# AS3364_DG412_bus_mixer_v1_4-4-layer.net
KiCad netlist of a schematic drawn in EAGLE
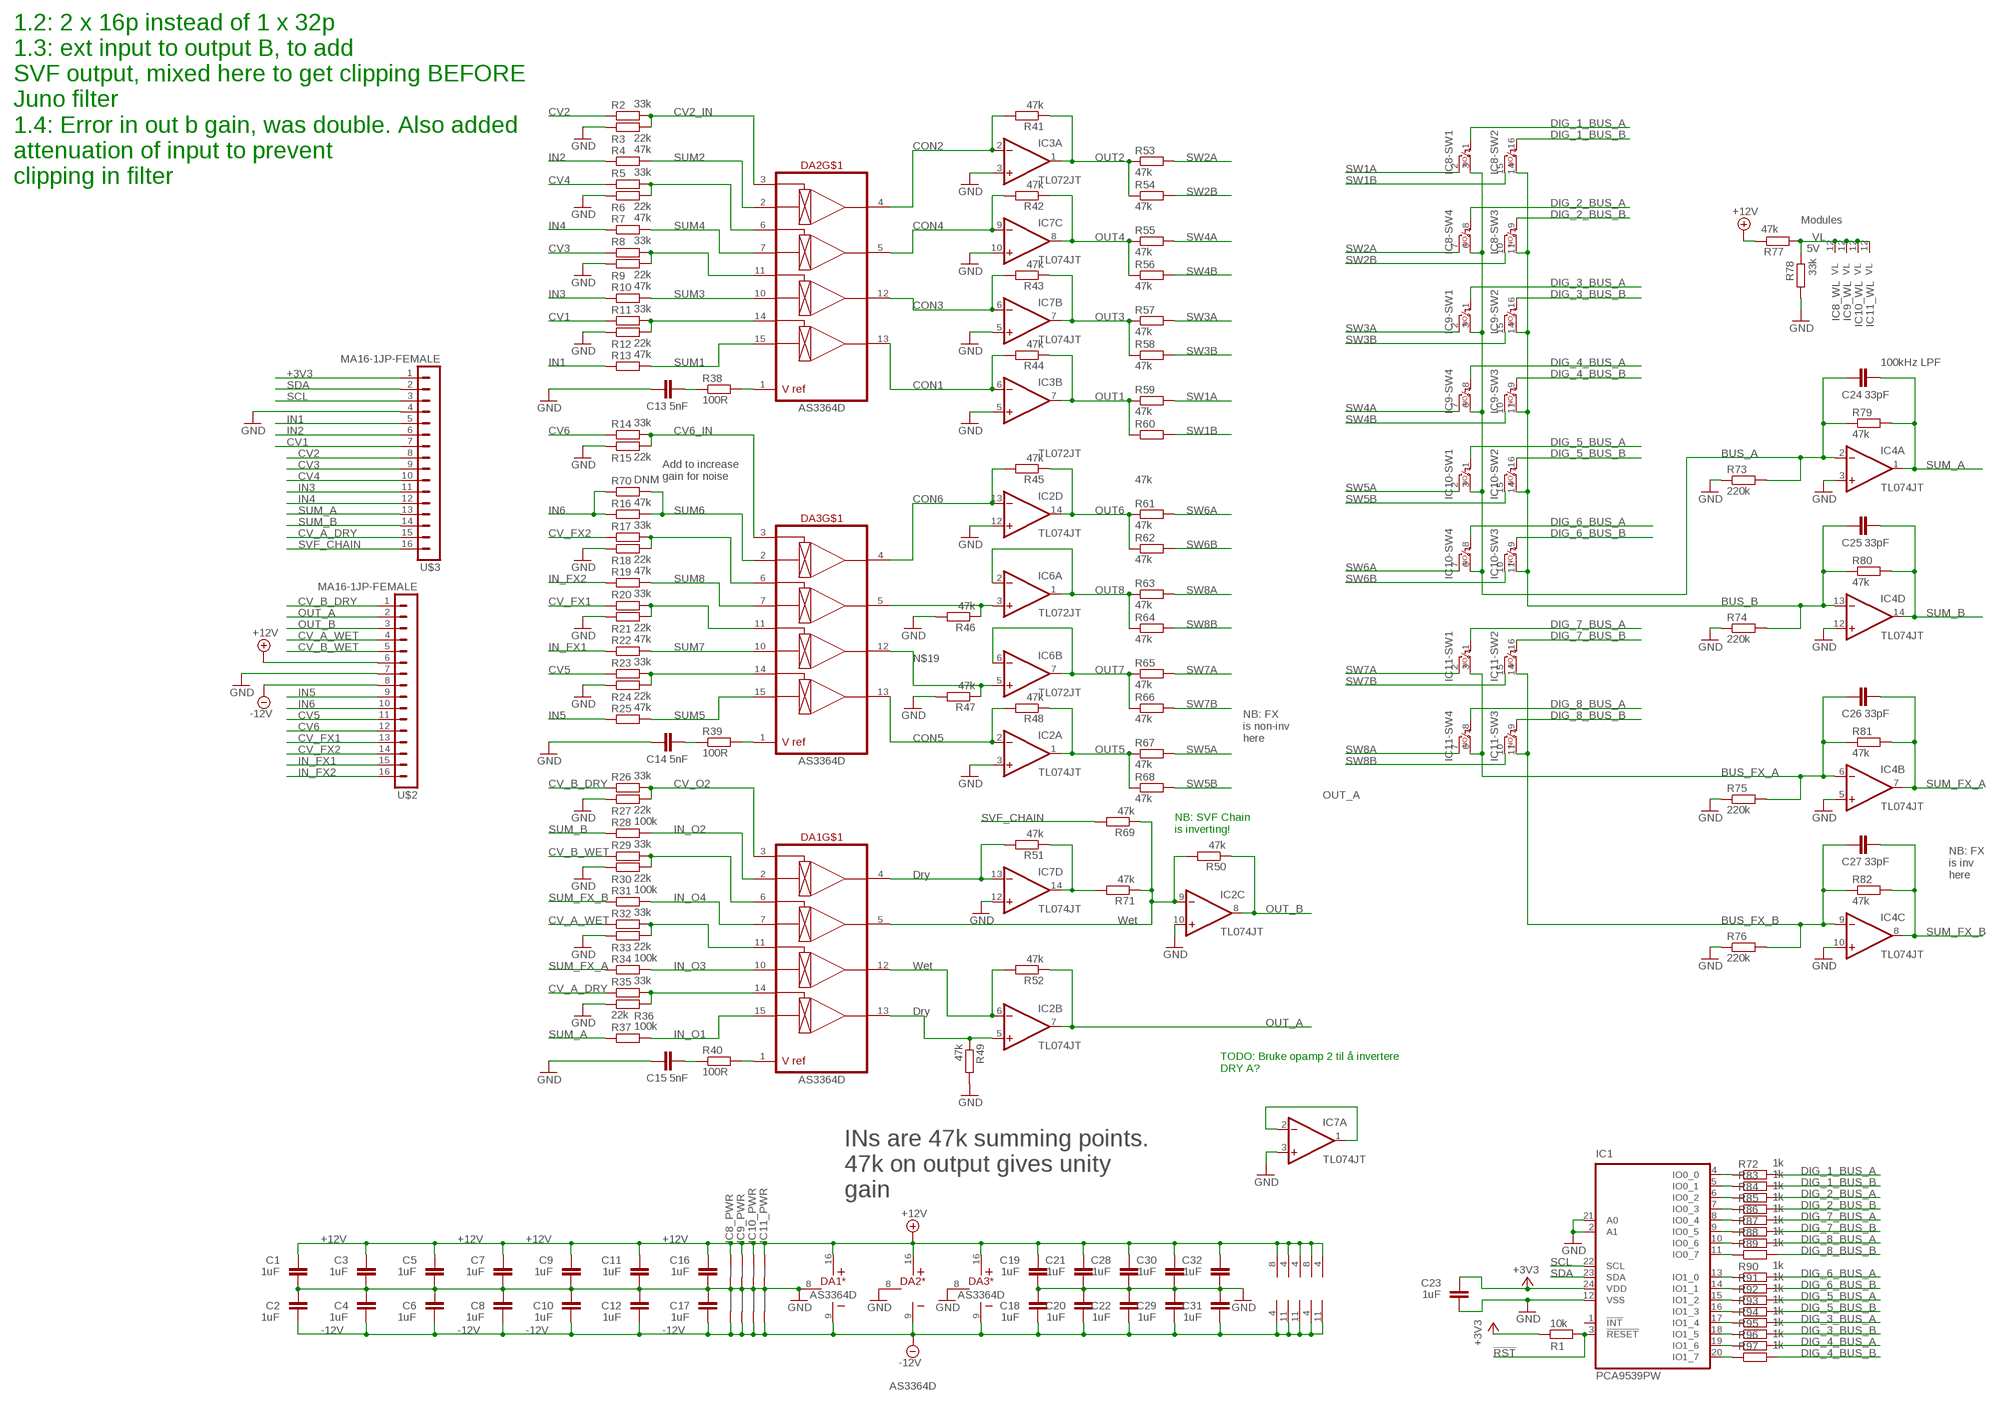
[diagram p0: schematic, sheet 1]

(export (version "E")
  (design (tool "Eeschema 10.0.6"))
  (components
    (comp (ref "C1")
      (value "1uF")
      (footprint "eagle-import:C0402-J")
      (libsource (lib "eagle-import") (part "C-EU-J0402"))
    )
    (comp (ref "C2")
      (value "1uF")
      (footprint "eagle-import:C0402-J")
      (libsource (lib "eagle-import") (part "C-EU-J0402"))
    )
    (comp (ref "C3")
      (value "1uF")
      (footprint "eagle-import:C0402-J")
      (libsource (lib "eagle-import") (part "C-EU-J0402"))
    )
    (comp (ref "C4")
      (value "1uF")
      (footprint "eagle-import:C0402-J")
      (libsource (lib "eagle-import") (part "C-EU-J0402"))
    )
    (comp (ref "C5")
      (value "1uF")
      (footprint "eagle-import:C0402-J")
      (libsource (lib "eagle-import") (part "C-EU-J0402"))
    )
    (comp (ref "C6")
      (value "1uF")
      (footprint "eagle-import:C0402-J")
      (libsource (lib "eagle-import") (part "C-EU-J0402"))
    )
    (comp (ref "C7")
      (value "1uF")
      (footprint "eagle-import:C0402-J")
      (libsource (lib "eagle-import") (part "C-EU-J0402"))
    )
    (comp (ref "C8")
      (value "1uF")
      (footprint "eagle-import:C0402-J")
      (libsource (lib "eagle-import") (part "C-EU-J0402"))
    )
    (comp (ref "C9")
      (value "1uF")
      (footprint "eagle-import:C0402-J")
      (libsource (lib "eagle-import") (part "C-EU-J0402"))
    )
    (comp (ref "C10")
      (value "1uF")
      (footprint "eagle-import:C0402-J")
      (libsource (lib "eagle-import") (part "C-EU-J0402"))
    )
    (comp (ref "C11")
      (value "1uF")
      (footprint "eagle-import:C0402-J")
      (libsource (lib "eagle-import") (part "C-EU-J0402"))
    )
    (comp (ref "C12")
      (value "1uF")
      (footprint "eagle-import:C0402-J")
      (libsource (lib "eagle-import") (part "C-EU-J0402"))
    )
    (comp (ref "C13")
      (value "5nF")
      (footprint "eagle-import:C0402-J")
      (libsource (lib "eagle-import") (part "C-EU-J0402"))
    )
    (comp (ref "C14")
      (value "5nF")
      (footprint "eagle-import:C0402-J")
      (libsource (lib "eagle-import") (part "C-EU-J0402"))
    )
    (comp (ref "C15")
      (value "5nF")
      (footprint "eagle-import:C0402-J")
      (libsource (lib "eagle-import") (part "C-EU-J0402"))
    )
    (comp (ref "C16")
      (value "1uF")
      (footprint "eagle-import:C0402-J")
      (libsource (lib "eagle-import") (part "C-EU-J0402"))
    )
    (comp (ref "C17")
      (value "1uF")
      (footprint "eagle-import:C0402-J")
      (libsource (lib "eagle-import") (part "C-EU-J0402"))
    )
    (comp (ref "C18")
      (value "1uF")
      (footprint "eagle-import:C0402-J")
      (libsource (lib "eagle-import") (part "C-EU-J0402"))
    )
    (comp (ref "C19")
      (value "1uF")
      (footprint "eagle-import:C0402-J")
      (libsource (lib "eagle-import") (part "C-EU-J0402"))
    )
    (comp (ref "C20")
      (value "1uF")
      (footprint "eagle-import:C0402-J")
      (libsource (lib "eagle-import") (part "C-EU-J0402"))
    )
    (comp (ref "C21")
      (value "1uF")
      (footprint "eagle-import:C0402-J")
      (libsource (lib "eagle-import") (part "C-EU-J0402"))
    )
    (comp (ref "C22")
      (value "1uF")
      (footprint "eagle-import:C0402-J")
      (libsource (lib "eagle-import") (part "C-EU-J0402"))
    )
    (comp (ref "C23")
      (value "1uF")
      (footprint "eagle-import:C0402-J")
      (libsource (lib "eagle-import") (part "C-EU-J0402"))
    )
    (comp (ref "C24")
      (value "33pF")
      (footprint "eagle-import:C0402-J")
      (libsource (lib "eagle-import") (part "C-EU-J0402"))
    )
    (comp (ref "C25")
      (value "33pF")
      (footprint "eagle-import:C0402-J")
      (libsource (lib "eagle-import") (part "C-EU-J0402"))
    )
    (comp (ref "C26")
      (value "33pF")
      (footprint "eagle-import:C0402-J")
      (libsource (lib "eagle-import") (part "C-EU-J0402"))
    )
    (comp (ref "C27")
      (value "33pF")
      (footprint "eagle-import:C0402-J")
      (libsource (lib "eagle-import") (part "C-EU-J0402"))
    )
    (comp (ref "C28")
      (value "1uF")
      (footprint "eagle-import:C0402-J")
      (libsource (lib "eagle-import") (part "C-EU-J0402"))
    )
    (comp (ref "C29")
      (value "1uF")
      (footprint "eagle-import:C0402-J")
      (libsource (lib "eagle-import") (part "C-EU-J0402"))
    )
    (comp (ref "C30")
      (value "1uF")
      (footprint "eagle-import:C0402-J")
      (libsource (lib "eagle-import") (part "C-EU-J0402"))
    )
    (comp (ref "C31")
      (value "1uF")
      (footprint "eagle-import:C0402-J")
      (libsource (lib "eagle-import") (part "C-EU-J0402"))
    )
    (comp (ref "C32")
      (value "1uF")
      (footprint "eagle-import:C0402-J")
      (libsource (lib "eagle-import") (part "C-EU-J0402"))
    )
    (comp (ref "DA1")
      (value "AS3364D")
      (footprint "eagle-import:DIL16J")
      (libsource (lib "eagle-import") (part "AS3364D"))
    )
    (comp (ref "DA2")
      (value "AS3364D")
      (footprint "eagle-import:DIL16J")
      (libsource (lib "eagle-import") (part "AS3364D"))
    )
    (comp (ref "DA3")
      (value "AS3364D")
      (footprint "eagle-import:DIL16J")
      (libsource (lib "eagle-import") (part "AS3364D"))
    )
    (comp (ref "IC1")
      (value "PCA9539PW")
      (footprint "eagle-import:TSSOP24J")
      (libsource (lib "eagle-import") (part "PCA9539PW"))
    )
    (comp (ref "IC2")
      (value "TL074JT")
      (footprint "eagle-import:TSSOP14J")
      (libsource (lib "eagle-import") (part "TL074JT"))
    )
    (comp (ref "IC3")
      (value "TL072JT")
      (footprint "eagle-import:TSSOP8J")
      (libsource (lib "eagle-import") (part "TL072JT"))
    )
    (comp (ref "IC4")
      (value "TL074JT")
      (footprint "eagle-import:TSSOP14J")
      (libsource (lib "eagle-import") (part "TL074JT"))
    )
    (comp (ref "IC6")
      (value "TL072JT")
      (footprint "eagle-import:TSSOP8J")
      (libsource (lib "eagle-import") (part "TL072JT"))
    )
    (comp (ref "IC7")
      (value "TL074JT")
      (footprint "eagle-import:TSSOP14J")
      (libsource (lib "eagle-import") (part "TL074JT"))
    )
    (comp (ref "IC8")
      (value "DG412-J")
      (footprint "eagle-import:DIL16J")
      (libsource (lib "eagle-import") (part "DG412-J"))
    )
    (comp (ref "IC9")
      (value "DG412-J")
      (footprint "eagle-import:DIL16J")
      (libsource (lib "eagle-import") (part "DG412-J"))
    )
    (comp (ref "IC10")
      (value "DG412-J")
      (footprint "eagle-import:DIL16J")
      (libsource (lib "eagle-import") (part "DG412-J"))
    )
    (comp (ref "IC11")
      (value "DG412-J")
      (footprint "eagle-import:DIL16J")
      (libsource (lib "eagle-import") (part "DG412-J"))
    )
    (comp (ref "R1")
      (value "10k")
      (footprint "eagle-import:R0402")
      (libsource (lib "eagle-import") (part "R-EU_R0402"))
    )
    (comp (ref "R2")
      (value "33k")
      (footprint "eagle-import:R0402")
      (libsource (lib "eagle-import") (part "R-EU_R0402"))
    )
    (comp (ref "R3")
      (value "22k")
      (footprint "eagle-import:R0402")
      (libsource (lib "eagle-import") (part "R-EU_R0402"))
    )
    (comp (ref "R4")
      (value "47k")
      (footprint "eagle-import:R0402")
      (libsource (lib "eagle-import") (part "R-EU_R0402"))
    )
    (comp (ref "R5")
      (value "33k")
      (footprint "eagle-import:R0402")
      (libsource (lib "eagle-import") (part "R-EU_R0402"))
    )
    (comp (ref "R6")
      (value "22k")
      (footprint "eagle-import:R0402")
      (libsource (lib "eagle-import") (part "R-EU_R0402"))
    )
    (comp (ref "R7")
      (value "47k")
      (footprint "eagle-import:R0402")
      (libsource (lib "eagle-import") (part "R-EU_R0402"))
    )
    (comp (ref "R8")
      (value "33k")
      (footprint "eagle-import:R0402")
      (libsource (lib "eagle-import") (part "R-EU_R0402"))
    )
    (comp (ref "R9")
      (value "22k")
      (footprint "eagle-import:R0402")
      (libsource (lib "eagle-import") (part "R-EU_R0402"))
    )
    (comp (ref "R10")
      (value "47k")
      (footprint "eagle-import:R0402")
      (libsource (lib "eagle-import") (part "R-EU_R0402"))
    )
    (comp (ref "R11")
      (value "33k")
      (footprint "eagle-import:R0402")
      (libsource (lib "eagle-import") (part "R-EU_R0402"))
    )
    (comp (ref "R12")
      (value "22k")
      (footprint "eagle-import:R0402")
      (libsource (lib "eagle-import") (part "R-EU_R0402"))
    )
    (comp (ref "R13")
      (value "47k")
      (footprint "eagle-import:R0402")
      (libsource (lib "eagle-import") (part "R-EU_R0402"))
    )
    (comp (ref "R14")
      (value "33k")
      (footprint "eagle-import:R0402")
      (libsource (lib "eagle-import") (part "R-EU_R0402"))
    )
    (comp (ref "R15")
      (value "22k")
      (footprint "eagle-import:R0402")
      (libsource (lib "eagle-import") (part "R-EU_R0402"))
    )
    (comp (ref "R16")
      (value "47k")
      (footprint "eagle-import:R0402")
      (libsource (lib "eagle-import") (part "R-EU_R0402"))
    )
    (comp (ref "R17")
      (value "33k")
      (footprint "eagle-import:R0402")
      (libsource (lib "eagle-import") (part "R-EU_R0402"))
    )
    (comp (ref "R18")
      (value "22k")
      (footprint "eagle-import:R0402")
      (libsource (lib "eagle-import") (part "R-EU_R0402"))
    )
    (comp (ref "R19")
      (value "47k")
      (footprint "eagle-import:R0402")
      (libsource (lib "eagle-import") (part "R-EU_R0402"))
    )
    (comp (ref "R20")
      (value "33k")
      (footprint "eagle-import:R0402")
      (libsource (lib "eagle-import") (part "R-EU_R0402"))
    )
    (comp (ref "R21")
      (value "22k")
      (footprint "eagle-import:R0402")
      (libsource (lib "eagle-import") (part "R-EU_R0402"))
    )
    (comp (ref "R22")
      (value "47k")
      (footprint "eagle-import:R0402")
      (libsource (lib "eagle-import") (part "R-EU_R0402"))
    )
    (comp (ref "R23")
      (value "33k")
      (footprint "eagle-import:R0402")
      (libsource (lib "eagle-import") (part "R-EU_R0402"))
    )
    (comp (ref "R24")
      (value "22k")
      (footprint "eagle-import:R0402")
      (libsource (lib "eagle-import") (part "R-EU_R0402"))
    )
    (comp (ref "R25")
      (value "47k")
      (footprint "eagle-import:R0402")
      (libsource (lib "eagle-import") (part "R-EU_R0402"))
    )
    (comp (ref "R26")
      (value "33k")
      (footprint "eagle-import:R0402")
      (libsource (lib "eagle-import") (part "R-EU_R0402"))
    )
    (comp (ref "R27")
      (value "22k")
      (footprint "eagle-import:R0402")
      (libsource (lib "eagle-import") (part "R-EU_R0402"))
    )
    (comp (ref "R28")
      (value "100k")
      (footprint "eagle-import:R0402")
      (libsource (lib "eagle-import") (part "R-EU_R0402"))
    )
    (comp (ref "R29")
      (value "33k")
      (footprint "eagle-import:R0402")
      (libsource (lib "eagle-import") (part "R-EU_R0402"))
    )
    (comp (ref "R30")
      (value "22k")
      (footprint "eagle-import:R0402")
      (libsource (lib "eagle-import") (part "R-EU_R0402"))
    )
    (comp (ref "R31")
      (value "100k")
      (footprint "eagle-import:R0402")
      (libsource (lib "eagle-import") (part "R-EU_R0402"))
    )
    (comp (ref "R32")
      (value "33k")
      (footprint "eagle-import:R0402")
      (libsource (lib "eagle-import") (part "R-EU_R0402"))
    )
    (comp (ref "R33")
      (value "22k")
      (footprint "eagle-import:R0402")
      (libsource (lib "eagle-import") (part "R-EU_R0402"))
    )
    (comp (ref "R34")
      (value "100k")
      (footprint "eagle-import:R0402")
      (libsource (lib "eagle-import") (part "R-EU_R0402"))
    )
    (comp (ref "R35")
      (value "33k")
      (footprint "eagle-import:R0402")
      (libsource (lib "eagle-import") (part "R-EU_R0402"))
    )
    (comp (ref "R36")
      (value "22k")
      (footprint "eagle-import:R0402")
      (libsource (lib "eagle-import") (part "R-EU_R0402"))
    )
    (comp (ref "R37")
      (value "100k")
      (footprint "eagle-import:R0402")
      (libsource (lib "eagle-import") (part "R-EU_R0402"))
    )
    (comp (ref "R38")
      (value "100R")
      (footprint "eagle-import:R0402")
      (libsource (lib "eagle-import") (part "R-EU_R0402"))
    )
    (comp (ref "R39")
      (value "100R")
      (footprint "eagle-import:R0402")
      (libsource (lib "eagle-import") (part "R-EU_R0402"))
    )
    (comp (ref "R40")
      (value "100R")
      (footprint "eagle-import:R0402")
      (libsource (lib "eagle-import") (part "R-EU_R0402"))
    )
    (comp (ref "R41")
      (value "47k")
      (footprint "eagle-import:R0402")
      (libsource (lib "eagle-import") (part "R-EU_R0402"))
    )
    (comp (ref "R42")
      (value "47k")
      (footprint "eagle-import:R0402")
      (libsource (lib "eagle-import") (part "R-EU_R0402"))
    )
    (comp (ref "R43")
      (value "47k")
      (footprint "eagle-import:R0402")
      (libsource (lib "eagle-import") (part "R-EU_R0402"))
    )
    (comp (ref "R44")
      (value "47k")
      (footprint "eagle-import:R0402")
      (libsource (lib "eagle-import") (part "R-EU_R0402"))
    )
    (comp (ref "R45")
      (value "47k")
      (footprint "eagle-import:R0402")
      (libsource (lib "eagle-import") (part "R-EU_R0402"))
    )
    (comp (ref "R46")
      (value "47k")
      (footprint "eagle-import:R0402")
      (libsource (lib "eagle-import") (part "R-EU_R0402"))
    )
    (comp (ref "R47")
      (value "47k")
      (footprint "eagle-import:R0402")
      (libsource (lib "eagle-import") (part "R-EU_R0402"))
    )
    (comp (ref "R48")
      (value "47k")
      (footprint "eagle-import:R0402")
      (libsource (lib "eagle-import") (part "R-EU_R0402"))
    )
    (comp (ref "R49")
      (value "47k")
      (footprint "eagle-import:R0402")
      (libsource (lib "eagle-import") (part "R-EU_R0402"))
    )
    (comp (ref "R50")
      (value "47k")
      (footprint "eagle-import:R0402")
      (libsource (lib "eagle-import") (part "R-EU_R0402"))
    )
    (comp (ref "R51")
      (value "47k")
      (footprint "eagle-import:R0402")
      (libsource (lib "eagle-import") (part "R-EU_R0402"))
    )
    (comp (ref "R52")
      (value "47k")
      (footprint "eagle-import:R0402")
      (libsource (lib "eagle-import") (part "R-EU_R0402"))
    )
    (comp (ref "R53")
      (value "47k")
      (footprint "eagle-import:R0402")
      (libsource (lib "eagle-import") (part "R-EU_R0402"))
    )
    (comp (ref "R54")
      (value "47k")
      (footprint "eagle-import:R0402")
      (libsource (lib "eagle-import") (part "R-EU_R0402"))
    )
    (comp (ref "R55")
      (value "47k")
      (footprint "eagle-import:R0402")
      (libsource (lib "eagle-import") (part "R-EU_R0402"))
    )
    (comp (ref "R56")
      (value "47k")
      (footprint "eagle-import:R0402")
      (libsource (lib "eagle-import") (part "R-EU_R0402"))
    )
    (comp (ref "R57")
      (value "47k")
      (footprint "eagle-import:R0402")
      (libsource (lib "eagle-import") (part "R-EU_R0402"))
    )
    (comp (ref "R58")
      (value "47k")
      (footprint "eagle-import:R0402")
      (libsource (lib "eagle-import") (part "R-EU_R0402"))
    )
    (comp (ref "R59")
      (value "47k")
      (footprint "eagle-import:R0402")
      (libsource (lib "eagle-import") (part "R-EU_R0402"))
    )
    (comp (ref "R60")
      (value "47k")
      (footprint "eagle-import:R0402")
      (libsource (lib "eagle-import") (part "R-EU_R0402"))
    )
    (comp (ref "R61")
      (value "47k")
      (footprint "eagle-import:R0402")
      (libsource (lib "eagle-import") (part "R-EU_R0402"))
    )
    (comp (ref "R62")
      (value "47k")
      (footprint "eagle-import:R0402")
      (libsource (lib "eagle-import") (part "R-EU_R0402"))
    )
    (comp (ref "R63")
      (value "47k")
      (footprint "eagle-import:R0402")
      (libsource (lib "eagle-import") (part "R-EU_R0402"))
    )
    (comp (ref "R64")
      (value "47k")
      (footprint "eagle-import:R0402")
      (libsource (lib "eagle-import") (part "R-EU_R0402"))
    )
    (comp (ref "R65")
      (value "47k")
      (footprint "eagle-import:R0402")
      (libsource (lib "eagle-import") (part "R-EU_R0402"))
    )
    (comp (ref "R66")
      (value "47k")
      (footprint "eagle-import:R0402")
      (libsource (lib "eagle-import") (part "R-EU_R0402"))
    )
    (comp (ref "R67")
      (value "47k")
      (footprint "eagle-import:R0402")
      (libsource (lib "eagle-import") (part "R-EU_R0402"))
    )
    (comp (ref "R68")
      (value "47k")
      (footprint "eagle-import:R0402")
      (libsource (lib "eagle-import") (part "R-EU_R0402"))
    )
    (comp (ref "R69")
      (value "47k")
      (footprint "eagle-import:R0402")
      (libsource (lib "eagle-import") (part "R-EU_R0402"))
    )
    (comp (ref "R70")
      (value "DNM")
      (footprint "eagle-import:R0805")
      (libsource (lib "eagle-import") (part "R-EU_R0805"))
    )
    (comp (ref "R71")
      (value "47k")
      (footprint "eagle-import:R0402")
      (libsource (lib "eagle-import") (part "R-EU_R0402"))
    )
    (comp (ref "R72")
      (value "1k")
      (footprint "eagle-import:R0402")
      (libsource (lib "eagle-import") (part "R-EU_R0402"))
    )
    (comp (ref "R73")
      (value "220k")
      (footprint "eagle-import:R0603")
      (libsource (lib "eagle-import") (part "R-EU_R0603"))
    )
    (comp (ref "R74")
      (value "220k")
      (footprint "eagle-import:R0603")
      (libsource (lib "eagle-import") (part "R-EU_R0603"))
    )
    (comp (ref "R75")
      (value "220k")
      (footprint "eagle-import:R0603")
      (libsource (lib "eagle-import") (part "R-EU_R0603"))
    )
    (comp (ref "R76")
      (value "220k")
      (footprint "eagle-import:R0603")
      (libsource (lib "eagle-import") (part "R-EU_R0603"))
    )
    (comp (ref "R77")
      (value "47k")
      (footprint "eagle-import:R0402")
      (libsource (lib "eagle-import") (part "R-EU_R0402"))
    )
    (comp (ref "R78")
      (value "33k")
      (footprint "eagle-import:R0402")
      (libsource (lib "eagle-import") (part "R-EU_R0402"))
    )
    (comp (ref "R79")
      (value "47k")
      (footprint "eagle-import:R0402")
      (libsource (lib "eagle-import") (part "R-EU_R0402"))
    )
    (comp (ref "R80")
      (value "47k")
      (footprint "eagle-import:R0402")
      (libsource (lib "eagle-import") (part "R-EU_R0402"))
    )
    (comp (ref "R81")
      (value "47k")
      (footprint "eagle-import:R0402")
      (libsource (lib "eagle-import") (part "R-EU_R0402"))
    )
    (comp (ref "R82")
      (value "47k")
      (footprint "eagle-import:R0402")
      (libsource (lib "eagle-import") (part "R-EU_R0402"))
    )
    (comp (ref "R83")
      (value "1k")
      (footprint "eagle-import:R0402")
      (libsource (lib "eagle-import") (part "R-EU_R0402"))
    )
    (comp (ref "R84")
      (value "1k")
      (footprint "eagle-import:R0402")
      (libsource (lib "eagle-import") (part "R-EU_R0402"))
    )
    (comp (ref "R85")
      (value "1k")
      (footprint "eagle-import:R0402")
      (libsource (lib "eagle-import") (part "R-EU_R0402"))
    )
    (comp (ref "R86")
      (value "1k")
      (footprint "eagle-import:R0402")
      (libsource (lib "eagle-import") (part "R-EU_R0402"))
    )
    (comp (ref "R87")
      (value "1k")
      (footprint "eagle-import:R0402")
      (libsource (lib "eagle-import") (part "R-EU_R0402"))
    )
    (comp (ref "R88")
      (value "1k")
      (footprint "eagle-import:R0402")
      (libsource (lib "eagle-import") (part "R-EU_R0402"))
    )
    (comp (ref "R89")
      (value "1k")
      (footprint "eagle-import:R0402")
      (libsource (lib "eagle-import") (part "R-EU_R0402"))
    )
    (comp (ref "R90")
      (value "1k")
      (footprint "eagle-import:R0402")
      (libsource (lib "eagle-import") (part "R-EU_R0402"))
    )
    (comp (ref "R91")
      (value "1k")
      (footprint "eagle-import:R0402")
      (libsource (lib "eagle-import") (part "R-EU_R0402"))
    )
    (comp (ref "R92")
      (value "1k")
      (footprint "eagle-import:R0402")
      (libsource (lib "eagle-import") (part "R-EU_R0402"))
    )
    (comp (ref "R93")
      (value "1k")
      (footprint "eagle-import:R0402")
      (libsource (lib "eagle-import") (part "R-EU_R0402"))
    )
    (comp (ref "R94")
      (value "1k")
      (footprint "eagle-import:R0402")
      (libsource (lib "eagle-import") (part "R-EU_R0402"))
    )
    (comp (ref "R95")
      (value "1k")
      (footprint "eagle-import:R0402")
      (libsource (lib "eagle-import") (part "R-EU_R0402"))
    )
    (comp (ref "R96")
      (value "1k")
      (footprint "eagle-import:R0402")
      (libsource (lib "eagle-import") (part "R-EU_R0402"))
    )
    (comp (ref "R97")
      (value "1k")
      (footprint "eagle-import:R0402")
      (libsource (lib "eagle-import") (part "R-EU_R0402"))
    )
    (comp (ref "U$2")
      (value "MA16-1JP-FEMALE")
      (footprint "eagle-import:SIP-PIN16-1J")
      (libsource (lib "eagle-import") (part "MA16-1JP"))
    )
    (comp (ref "U$3")
      (value "MA16-1JP-FEMALE")
      (footprint "eagle-import:SIP-PIN16-1J")
      (libsource (lib "eagle-import") (part "MA16-1JP"))
    )
  )
  (nets
    (net (code "1") (name "+3V3") (class "Default")
      (node (ref "C23") (pin "2") (pinfunction "2_2") (pintype "passive"))
      (node (ref "IC1") (pin "24") (pinfunction "VDD_24") (pintype "power_in"))
      (node (ref "R1") (pin "1") (pinfunction "1_1") (pintype "passive"))
      (node (ref "U$3") (pin "1") (pinfunction "1_1") (pintype "passive"))
    )
    (net (code "2") (name "+12V") (class "Default")
      (node (ref "C1") (pin "2") (pinfunction "2_2") (pintype "passive"))
      (node (ref "C11") (pin "2") (pinfunction "2_2") (pintype "passive"))
      (node (ref "C16") (pin "2") (pinfunction "2_2") (pintype "passive"))
      (node (ref "C19") (pin "2") (pinfunction "2_2") (pintype "passive"))
      (node (ref "C21") (pin "2") (pinfunction "2_2") (pintype "passive"))
      (node (ref "C28") (pin "2") (pinfunction "2_2") (pintype "passive"))
      (node (ref "C3") (pin "2") (pinfunction "2_2") (pintype "passive"))
      (node (ref "C30") (pin "2") (pinfunction "2_2") (pintype "passive"))
      (node (ref "C32") (pin "2") (pinfunction "2_2") (pintype "passive"))
      (node (ref "C5") (pin "2") (pinfunction "2_2") (pintype "passive"))
      (node (ref "C7") (pin "2") (pinfunction "2_2") (pintype "passive"))
      (node (ref "C9") (pin "2") (pinfunction "2_2") (pintype "passive"))
      (node (ref "DA1") (pin "16") (pinfunction "V+_16") (pintype "power_in"))
      (node (ref "DA2") (pin "16") (pinfunction "V+_16") (pintype "power_in"))
      (node (ref "DA3") (pin "16") (pinfunction "V+_16") (pintype "power_in"))
      (node (ref "IC10") (pin "13") (pinfunction "+15V_13") (pintype "power_in"))
      (node (ref "IC11") (pin "13") (pinfunction "+15V_13") (pintype "power_in"))
      (node (ref "IC2") (pin "4") (pinfunction "V+_4") (pintype "power_in"))
      (node (ref "IC3") (pin "8") (pinfunction "V+_8") (pintype "power_in"))
      (node (ref "IC4") (pin "4") (pinfunction "V+_4") (pintype "power_in"))
      (node (ref "IC6") (pin "8") (pinfunction "V+_8") (pintype "power_in"))
      (node (ref "IC7") (pin "4") (pinfunction "V+_4") (pintype "power_in"))
      (node (ref "IC8") (pin "13") (pinfunction "+15V_13") (pintype "power_in"))
      (node (ref "IC9") (pin "13") (pinfunction "+15V_13") (pintype "power_in"))
      (node (ref "R77") (pin "1") (pinfunction "1_1") (pintype "passive"))
      (node (ref "U$2") (pin "6") (pinfunction "6_6") (pintype "passive"))
    )
    (net (code "3") (name "-12V") (class "Default")
      (node (ref "C10") (pin "1") (pinfunction "1_1") (pintype "passive"))
      (node (ref "C12") (pin "1") (pinfunction "1_1") (pintype "passive"))
      (node (ref "C17") (pin "1") (pinfunction "1_1") (pintype "passive"))
      (node (ref "C18") (pin "1") (pinfunction "1_1") (pintype "passive"))
      (node (ref "C2") (pin "1") (pinfunction "1_1") (pintype "passive"))
      (node (ref "C20") (pin "1") (pinfunction "1_1") (pintype "passive"))
      (node (ref "C22") (pin "1") (pinfunction "1_1") (pintype "passive"))
      (node (ref "C29") (pin "1") (pinfunction "1_1") (pintype "passive"))
      (node (ref "C31") (pin "1") (pinfunction "1_1") (pintype "passive"))
      (node (ref "C4") (pin "1") (pinfunction "1_1") (pintype "passive"))
      (node (ref "C6") (pin "1") (pinfunction "1_1") (pintype "passive"))
      (node (ref "C8") (pin "1") (pinfunction "1_1") (pintype "passive"))
      (node (ref "DA1") (pin "9") (pinfunction "V-_9") (pintype "power_in"))
      (node (ref "DA2") (pin "9") (pinfunction "V-_9") (pintype "power_in"))
      (node (ref "DA3") (pin "9") (pinfunction "V-_9") (pintype "power_in"))
      (node (ref "IC10") (pin "4") (pinfunction "-15V_4") (pintype "power_in"))
      (node (ref "IC11") (pin "4") (pinfunction "-15V_4") (pintype "power_in"))
      (node (ref "IC2") (pin "11") (pinfunction "V-_11") (pintype "power_in"))
      (node (ref "IC3") (pin "4") (pinfunction "V-_4") (pintype "power_in"))
      (node (ref "IC4") (pin "11") (pinfunction "V-_11") (pintype "power_in"))
      (node (ref "IC6") (pin "4") (pinfunction "V-_4") (pintype "power_in"))
      (node (ref "IC7") (pin "11") (pinfunction "V-_11") (pintype "power_in"))
      (node (ref "IC8") (pin "4") (pinfunction "-15V_4") (pintype "power_in"))
      (node (ref "IC9") (pin "4") (pinfunction "-15V_4") (pintype "power_in"))
      (node (ref "U$2") (pin "8") (pinfunction "8_8") (pintype "passive"))
    )
    (net (code "4") (name "/BUS_A") (class "Default")
      (node (ref "C24") (pin "1") (pinfunction "1_1") (pintype "passive"))
      (node (ref "IC10") (pin "3") (pinfunction "S_3") (pintype "bidirectional"))
      (node (ref "IC10") (pin "6") (pinfunction "S_6") (pintype "bidirectional"))
      (node (ref "IC4") (pin "2") (pinfunction "-IN_2") (pintype "input"))
      (node (ref "IC8") (pin "3") (pinfunction "S_3") (pintype "bidirectional"))
      (node (ref "IC8") (pin "6") (pinfunction "S_6") (pintype "bidirectional"))
      (node (ref "IC9") (pin "3") (pinfunction "S_3") (pintype "bidirectional"))
      (node (ref "IC9") (pin "6") (pinfunction "S_6") (pintype "bidirectional"))
      (node (ref "R73") (pin "2") (pinfunction "2_2") (pintype "passive"))
      (node (ref "R79") (pin "1") (pinfunction "1_1") (pintype "passive"))
    )
    (net (code "5") (name "/BUS_B") (class "Default")
      (node (ref "C25") (pin "1") (pinfunction "1_1") (pintype "passive"))
      (node (ref "IC10") (pin "11") (pinfunction "S_11") (pintype "bidirectional"))
      (node (ref "IC10") (pin "14") (pinfunction "S_14") (pintype "bidirectional"))
      (node (ref "IC4") (pin "13") (pinfunction "-IN_13") (pintype "input"))
      (node (ref "IC8") (pin "11") (pinfunction "S_11") (pintype "bidirectional"))
      (node (ref "IC8") (pin "14") (pinfunction "S_14") (pintype "bidirectional"))
      (node (ref "IC9") (pin "11") (pinfunction "S_11") (pintype "bidirectional"))
      (node (ref "IC9") (pin "14") (pinfunction "S_14") (pintype "bidirectional"))
      (node (ref "R74") (pin "2") (pinfunction "2_2") (pintype "passive"))
      (node (ref "R80") (pin "1") (pinfunction "1_1") (pintype "passive"))
    )
    (net (code "6") (name "/BUS_FX_A") (class "Default")
      (node (ref "C26") (pin "1") (pinfunction "1_1") (pintype "passive"))
      (node (ref "IC11") (pin "3") (pinfunction "S_3") (pintype "bidirectional"))
      (node (ref "IC11") (pin "6") (pinfunction "S_6") (pintype "bidirectional"))
      (node (ref "IC4") (pin "6") (pinfunction "-IN_6") (pintype "input"))
      (node (ref "R75") (pin "2") (pinfunction "2_2") (pintype "passive"))
      (node (ref "R81") (pin "1") (pinfunction "1_1") (pintype "passive"))
    )
    (net (code "7") (name "/BUS_FX_B") (class "Default")
      (node (ref "C27") (pin "1") (pinfunction "1_1") (pintype "passive"))
      (node (ref "IC11") (pin "11") (pinfunction "S_11") (pintype "bidirectional"))
      (node (ref "IC11") (pin "14") (pinfunction "S_14") (pintype "bidirectional"))
      (node (ref "IC4") (pin "9") (pinfunction "-IN_9") (pintype "input"))
      (node (ref "R76") (pin "2") (pinfunction "2_2") (pintype "passive"))
      (node (ref "R82") (pin "1") (pinfunction "1_1") (pintype "passive"))
    )
    (net (code "8") (name "/CON1") (class "Default")
      (node (ref "DA2") (pin "13") (pinfunction "OUT4_13") (pintype "output"))
      (node (ref "IC3") (pin "6") (pinfunction "-IN_6") (pintype "input"))
      (node (ref "R44") (pin "2") (pinfunction "2_2") (pintype "passive"))
    )
    (net (code "9") (name "/CON2") (class "Default")
      (node (ref "DA2") (pin "4") (pinfunction "OUT1_4") (pintype "output"))
      (node (ref "IC3") (pin "2") (pinfunction "-IN_2") (pintype "input"))
      (node (ref "R41") (pin "2") (pinfunction "2_2") (pintype "passive"))
    )
    (net (code "10") (name "/CON3") (class "Default")
      (node (ref "DA2") (pin "12") (pinfunction "OUT3_12") (pintype "output"))
      (node (ref "IC7") (pin "6") (pinfunction "-IN_6") (pintype "input"))
      (node (ref "R43") (pin "2") (pinfunction "2_2") (pintype "passive"))
    )
    (net (code "11") (name "/CON4") (class "Default")
      (node (ref "DA2") (pin "5") (pinfunction "OUT2_5") (pintype "output"))
      (node (ref "IC7") (pin "9") (pinfunction "-IN_9") (pintype "input"))
      (node (ref "R42") (pin "2") (pinfunction "2_2") (pintype "passive"))
    )
    (net (code "12") (name "/CON5") (class "Default")
      (node (ref "DA3") (pin "13") (pinfunction "OUT4_13") (pintype "output"))
      (node (ref "IC2") (pin "2") (pinfunction "-IN_2") (pintype "input"))
      (node (ref "R48") (pin "2") (pinfunction "2_2") (pintype "passive"))
    )
    (net (code "13") (name "/CON6") (class "Default")
      (node (ref "DA3") (pin "4") (pinfunction "OUT1_4") (pintype "output"))
      (node (ref "IC2") (pin "13") (pinfunction "-IN_13") (pintype "input"))
      (node (ref "R45") (pin "2") (pinfunction "2_2") (pintype "passive"))
    )
    (net (code "14") (name "/CV1") (class "Default")
      (node (ref "R11") (pin "1") (pinfunction "1_1") (pintype "passive"))
      (node (ref "U$3") (pin "7") (pinfunction "7_7") (pintype "passive"))
    )
    (net (code "15") (name "/CV2") (class "Default")
      (node (ref "R2") (pin "1") (pinfunction "1_1") (pintype "passive"))
      (node (ref "U$3") (pin "8") (pinfunction "8_8") (pintype "passive"))
    )
    (net (code "16") (name "/CV2_IN") (class "Default")
      (node (ref "DA2") (pin "3") (pinfunction "CV1_3") (pintype "input"))
      (node (ref "R2") (pin "2") (pinfunction "2_2") (pintype "passive"))
      (node (ref "R3") (pin "2") (pinfunction "2_2") (pintype "passive"))
    )
    (net (code "17") (name "/CV3") (class "Default")
      (node (ref "R8") (pin "1") (pinfunction "1_1") (pintype "passive"))
      (node (ref "U$3") (pin "9") (pinfunction "9_9") (pintype "passive"))
    )
    (net (code "18") (name "/CV4") (class "Default")
      (node (ref "R5") (pin "1") (pinfunction "1_1") (pintype "passive"))
      (node (ref "U$3") (pin "10") (pinfunction "10_10") (pintype "passive"))
    )
    (net (code "19") (name "/CV5") (class "Default")
      (node (ref "R23") (pin "1") (pinfunction "1_1") (pintype "passive"))
      (node (ref "U$2") (pin "11") (pinfunction "11_11") (pintype "passive"))
    )
    (net (code "20") (name "/CV6") (class "Default")
      (node (ref "R14") (pin "1") (pinfunction "1_1") (pintype "passive"))
      (node (ref "U$2") (pin "12") (pinfunction "12_12") (pintype "passive"))
    )
    (net (code "21") (name "/CV6_IN") (class "Default")
      (node (ref "DA3") (pin "3") (pinfunction "CV1_3") (pintype "input"))
      (node (ref "R14") (pin "2") (pinfunction "2_2") (pintype "passive"))
      (node (ref "R15") (pin "2") (pinfunction "2_2") (pintype "passive"))
    )
    (net (code "22") (name "/CV_A_DRY") (class "Default")
      (node (ref "R35") (pin "1") (pinfunction "1_1") (pintype "passive"))
      (node (ref "U$3") (pin "15") (pinfunction "15_15") (pintype "passive"))
    )
    (net (code "23") (name "/CV_A_WET") (class "Default")
      (node (ref "R32") (pin "1") (pinfunction "1_1") (pintype "passive"))
      (node (ref "U$2") (pin "4") (pinfunction "4_4") (pintype "passive"))
    )
    (net (code "24") (name "/CV_B_DRY") (class "Default")
      (node (ref "R26") (pin "1") (pinfunction "1_1") (pintype "passive"))
      (node (ref "U$2") (pin "1") (pinfunction "1_1") (pintype "passive"))
    )
    (net (code "25") (name "/CV_B_WET") (class "Default")
      (node (ref "R29") (pin "1") (pinfunction "1_1") (pintype "passive"))
      (node (ref "U$2") (pin "5") (pinfunction "5_5") (pintype "passive"))
    )
    (net (code "26") (name "/CV_FX1") (class "Default")
      (node (ref "R20") (pin "1") (pinfunction "1_1") (pintype "passive"))
      (node (ref "U$2") (pin "13") (pinfunction "13_13") (pintype "passive"))
    )
    (net (code "27") (name "/CV_FX2") (class "Default")
      (node (ref "R17") (pin "1") (pinfunction "1_1") (pintype "passive"))
      (node (ref "U$2") (pin "14") (pinfunction "14_14") (pintype "passive"))
    )
    (net (code "28") (name "/CV_O2") (class "Default")
      (node (ref "DA1") (pin "3") (pinfunction "CV1_3") (pintype "input"))
      (node (ref "R26") (pin "2") (pinfunction "2_2") (pintype "passive"))
      (node (ref "R27") (pin "2") (pinfunction "2_2") (pintype "passive"))
    )
    (net (code "29") (name "/DIG_1_BUS_A") (class "Default")
      (node (ref "IC8") (pin "1") (pinfunction "C_1") (pintype "bidirectional"))
      (node (ref "R72") (pin "2") (pinfunction "2_2") (pintype "passive"))
    )
    (net (code "30") (name "/DIG_1_BUS_B") (class "Default")
      (node (ref "IC8") (pin "16") (pinfunction "C_16") (pintype "bidirectional"))
      (node (ref "R83") (pin "2") (pinfunction "2_2") (pintype "passive"))
    )
    (net (code "31") (name "/DIG_2_BUS_A") (class "Default")
      (node (ref "IC8") (pin "8") (pinfunction "C_8") (pintype "bidirectional"))
      (node (ref "R84") (pin "2") (pinfunction "2_2") (pintype "passive"))
    )
    (net (code "32") (name "/DIG_2_BUS_B") (class "Default")
      (node (ref "IC8") (pin "9") (pinfunction "C_9") (pintype "bidirectional"))
      (node (ref "R85") (pin "2") (pinfunction "2_2") (pintype "passive"))
    )
    (net (code "33") (name "/DIG_3_BUS_A") (class "Default")
      (node (ref "IC9") (pin "1") (pinfunction "C_1") (pintype "bidirectional"))
      (node (ref "R94") (pin "2") (pinfunction "2_2") (pintype "passive"))
    )
    (net (code "34") (name "/DIG_3_BUS_B") (class "Default")
      (node (ref "IC9") (pin "16") (pinfunction "C_16") (pintype "bidirectional"))
      (node (ref "R95") (pin "2") (pinfunction "2_2") (pintype "passive"))
    )
    (net (code "35") (name "/DIG_4_BUS_A") (class "Default")
      (node (ref "IC9") (pin "8") (pinfunction "C_8") (pintype "bidirectional"))
      (node (ref "R96") (pin "2") (pinfunction "2_2") (pintype "passive"))
    )
    (net (code "36") (name "/DIG_4_BUS_B") (class "Default")
      (node (ref "IC9") (pin "9") (pinfunction "C_9") (pintype "bidirectional"))
      (node (ref "R97") (pin "2") (pinfunction "2_2") (pintype "passive"))
    )
    (net (code "37") (name "/DIG_5_BUS_A") (class "Default")
      (node (ref "IC10") (pin "1") (pinfunction "C_1") (pintype "bidirectional"))
      (node (ref "R92") (pin "2") (pinfunction "2_2") (pintype "passive"))
    )
    (net (code "38") (name "/DIG_5_BUS_B") (class "Default")
      (node (ref "IC10") (pin "16") (pinfunction "C_16") (pintype "bidirectional"))
      (node (ref "R93") (pin "2") (pinfunction "2_2") (pintype "passive"))
    )
    (net (code "39") (name "/DIG_6_BUS_A") (class "Default")
      (node (ref "IC10") (pin "8") (pinfunction "C_8") (pintype "bidirectional"))
      (node (ref "R90") (pin "2") (pinfunction "2_2") (pintype "passive"))
    )
    (net (code "40") (name "/DIG_6_BUS_B") (class "Default")
      (node (ref "IC10") (pin "9") (pinfunction "C_9") (pintype "bidirectional"))
      (node (ref "R91") (pin "2") (pinfunction "2_2") (pintype "passive"))
    )
    (net (code "41") (name "/DIG_7_BUS_A") (class "Default")
      (node (ref "IC11") (pin "1") (pinfunction "C_1") (pintype "bidirectional"))
      (node (ref "R86") (pin "2") (pinfunction "2_2") (pintype "passive"))
    )
    (net (code "42") (name "/DIG_7_BUS_B") (class "Default")
      (node (ref "IC11") (pin "16") (pinfunction "C_16") (pintype "bidirectional"))
      (node (ref "R87") (pin "2") (pinfunction "2_2") (pintype "passive"))
    )
    (net (code "43") (name "/DIG_8_BUS_A") (class "Default")
      (node (ref "IC11") (pin "8") (pinfunction "C_8") (pintype "bidirectional"))
      (node (ref "R88") (pin "2") (pinfunction "2_2") (pintype "passive"))
    )
    (net (code "44") (name "/DIG_8_BUS_B") (class "Default")
      (node (ref "IC11") (pin "9") (pinfunction "C_9") (pintype "bidirectional"))
      (node (ref "R89") (pin "2") (pinfunction "2_2") (pintype "passive"))
    )
    (net (code "45") (name "/IN1") (class "Default")
      (node (ref "R13") (pin "1") (pinfunction "1_1") (pintype "passive"))
      (node (ref "U$3") (pin "5") (pinfunction "5_5") (pintype "passive"))
    )
    (net (code "46") (name "/IN2") (class "Default")
      (node (ref "R4") (pin "1") (pinfunction "1_1") (pintype "passive"))
      (node (ref "U$3") (pin "6") (pinfunction "6_6") (pintype "passive"))
    )
    (net (code "47") (name "/IN3") (class "Default")
      (node (ref "R10") (pin "1") (pinfunction "1_1") (pintype "passive"))
      (node (ref "U$3") (pin "11") (pinfunction "11_11") (pintype "passive"))
    )
    (net (code "48") (name "/IN4") (class "Default")
      (node (ref "R7") (pin "1") (pinfunction "1_1") (pintype "passive"))
      (node (ref "U$3") (pin "12") (pinfunction "12_12") (pintype "passive"))
    )
    (net (code "49") (name "/IN5") (class "Default")
      (node (ref "R25") (pin "1") (pinfunction "1_1") (pintype "passive"))
      (node (ref "U$2") (pin "9") (pinfunction "9_9") (pintype "passive"))
    )
    (net (code "50") (name "/IN6") (class "Default")
      (node (ref "R16") (pin "1") (pinfunction "1_1") (pintype "passive"))
      (node (ref "R70") (pin "1") (pinfunction "1_1") (pintype "passive"))
      (node (ref "U$2") (pin "10") (pinfunction "10_10") (pintype "passive"))
    )
    (net (code "51") (name "/IN_FX1") (class "Default")
      (node (ref "R22") (pin "1") (pinfunction "1_1") (pintype "passive"))
      (node (ref "U$2") (pin "15") (pinfunction "15_15") (pintype "passive"))
    )
    (net (code "52") (name "/IN_FX2") (class "Default")
      (node (ref "R19") (pin "1") (pinfunction "1_1") (pintype "passive"))
      (node (ref "U$2") (pin "16") (pinfunction "16_16") (pintype "passive"))
    )
    (net (code "53") (name "/IN_O1") (class "Default")
      (node (ref "DA1") (pin "15") (pinfunction "IN4_15") (pintype "input"))
      (node (ref "R37") (pin "2") (pinfunction "2_2") (pintype "passive"))
    )
    (net (code "54") (name "/IN_O2") (class "Default")
      (node (ref "DA1") (pin "2") (pinfunction "IN1_2") (pintype "input"))
      (node (ref "R28") (pin "2") (pinfunction "2_2") (pintype "passive"))
    )
    (net (code "55") (name "/IN_O3") (class "Default")
      (node (ref "DA1") (pin "10") (pinfunction "IN3_10") (pintype "input"))
      (node (ref "R34") (pin "2") (pinfunction "2_2") (pintype "passive"))
    )
    (net (code "56") (name "/IN_O4") (class "Default")
      (node (ref "DA1") (pin "7") (pinfunction "IN2_7") (pintype "input"))
      (node (ref "R31") (pin "2") (pinfunction "2_2") (pintype "passive"))
    )
    (net (code "57") (name "/N$19") (class "Default")
      (node (ref "DA3") (pin "12") (pinfunction "OUT3_12") (pintype "output"))
      (node (ref "IC6") (pin "5") (pinfunction "+IN_5") (pintype "input"))
      (node (ref "R47") (pin "1") (pinfunction "1_1") (pintype "passive"))
    )
    (net (code "58") (name "/OUT1") (class "Default")
      (node (ref "IC3") (pin "7") (pinfunction "OUT_7") (pintype "output"))
      (node (ref "R44") (pin "1") (pinfunction "1_1") (pintype "passive"))
      (node (ref "R59") (pin "1") (pinfunction "1_1") (pintype "passive"))
      (node (ref "R60") (pin "1") (pinfunction "1_1") (pintype "passive"))
    )
    (net (code "59") (name "/OUT2") (class "Default")
      (node (ref "IC3") (pin "1") (pinfunction "OUT_1") (pintype "output"))
      (node (ref "R41") (pin "1") (pinfunction "1_1") (pintype "passive"))
      (node (ref "R53") (pin "1") (pinfunction "1_1") (pintype "passive"))
      (node (ref "R54") (pin "1") (pinfunction "1_1") (pintype "passive"))
    )
    (net (code "60") (name "/OUT3") (class "Default")
      (node (ref "IC7") (pin "7") (pinfunction "OUT_7") (pintype "output"))
      (node (ref "R43") (pin "1") (pinfunction "1_1") (pintype "passive"))
      (node (ref "R57") (pin "1") (pinfunction "1_1") (pintype "passive"))
      (node (ref "R58") (pin "1") (pinfunction "1_1") (pintype "passive"))
    )
    (net (code "61") (name "/OUT4") (class "Default")
      (node (ref "IC7") (pin "8") (pinfunction "OUT_8") (pintype "output"))
      (node (ref "R42") (pin "1") (pinfunction "1_1") (pintype "passive"))
      (node (ref "R55") (pin "1") (pinfunction "1_1") (pintype "passive"))
      (node (ref "R56") (pin "1") (pinfunction "1_1") (pintype "passive"))
    )
    (net (code "62") (name "/OUT5") (class "Default")
      (node (ref "IC2") (pin "1") (pinfunction "OUT_1") (pintype "output"))
      (node (ref "R48") (pin "1") (pinfunction "1_1") (pintype "passive"))
      (node (ref "R67") (pin "1") (pinfunction "1_1") (pintype "passive"))
      (node (ref "R68") (pin "1") (pinfunction "1_1") (pintype "passive"))
    )
    (net (code "63") (name "/OUT6") (class "Default")
      (node (ref "IC2") (pin "14") (pinfunction "OUT_14") (pintype "output"))
      (node (ref "R45") (pin "1") (pinfunction "1_1") (pintype "passive"))
      (node (ref "R61") (pin "1") (pinfunction "1_1") (pintype "passive"))
      (node (ref "R62") (pin "1") (pinfunction "1_1") (pintype "passive"))
    )
    (net (code "64") (name "/OUT7") (class "Default")
      (node (ref "IC6") (pin "6") (pinfunction "-IN_6") (pintype "input"))
      (node (ref "IC6") (pin "7") (pinfunction "OUT_7") (pintype "output"))
      (node (ref "R65") (pin "1") (pinfunction "1_1") (pintype "passive"))
      (node (ref "R66") (pin "1") (pinfunction "1_1") (pintype "passive"))
    )
    (net (code "65") (name "/OUT8") (class "Default")
      (node (ref "IC6") (pin "1") (pinfunction "OUT_1") (pintype "output"))
      (node (ref "IC6") (pin "2") (pinfunction "-IN_2") (pintype "input"))
      (node (ref "R63") (pin "1") (pinfunction "1_1") (pintype "passive"))
      (node (ref "R64") (pin "1") (pinfunction "1_1") (pintype "passive"))
    )
    (net (code "66") (name "/OUT_A") (class "Default")
      (node (ref "IC2") (pin "7") (pinfunction "OUT_7") (pintype "output"))
      (node (ref "R52") (pin "1") (pinfunction "1_1") (pintype "passive"))
      (node (ref "U$2") (pin "2") (pinfunction "2_2") (pintype "passive"))
    )
    (net (code "67") (name "/OUT_B") (class "Default")
      (node (ref "IC2") (pin "8") (pinfunction "OUT_8") (pintype "output"))
      (node (ref "R50") (pin "1") (pinfunction "1_1") (pintype "passive"))
      (node (ref "U$2") (pin "3") (pinfunction "3_3") (pintype "passive"))
    )
    (net (code "68") (name "/SCL") (class "Default")
      (node (ref "IC1") (pin "22") (pinfunction "SCL_22") (pintype "bidirectional"))
      (node (ref "U$3") (pin "3") (pinfunction "3_3") (pintype "passive"))
    )
    (net (code "69") (name "/SDA") (class "Default")
      (node (ref "IC1") (pin "23") (pinfunction "SDA_23") (pintype "bidirectional"))
      (node (ref "U$3") (pin "2") (pinfunction "2_2") (pintype "passive"))
    )
    (net (code "70") (name "/SUM1") (class "Default")
      (node (ref "DA2") (pin "15") (pinfunction "IN4_15") (pintype "input"))
      (node (ref "R13") (pin "2") (pinfunction "2_2") (pintype "passive"))
    )
    (net (code "71") (name "/SUM2") (class "Default")
      (node (ref "DA2") (pin "2") (pinfunction "IN1_2") (pintype "input"))
      (node (ref "R4") (pin "2") (pinfunction "2_2") (pintype "passive"))
    )
    (net (code "72") (name "/SUM3") (class "Default")
      (node (ref "DA2") (pin "10") (pinfunction "IN3_10") (pintype "input"))
      (node (ref "R10") (pin "2") (pinfunction "2_2") (pintype "passive"))
    )
    (net (code "73") (name "/SUM4") (class "Default")
      (node (ref "DA2") (pin "7") (pinfunction "IN2_7") (pintype "input"))
      (node (ref "R7") (pin "2") (pinfunction "2_2") (pintype "passive"))
    )
    (net (code "74") (name "/SUM5") (class "Default")
      (node (ref "DA3") (pin "15") (pinfunction "IN4_15") (pintype "input"))
      (node (ref "R25") (pin "2") (pinfunction "2_2") (pintype "passive"))
    )
    (net (code "75") (name "/SUM6") (class "Default")
      (node (ref "DA3") (pin "2") (pinfunction "IN1_2") (pintype "input"))
      (node (ref "R16") (pin "2") (pinfunction "2_2") (pintype "passive"))
      (node (ref "R70") (pin "2") (pinfunction "2_2") (pintype "passive"))
    )
    (net (code "76") (name "/SUM7") (class "Default")
      (node (ref "DA3") (pin "10") (pinfunction "IN3_10") (pintype "input"))
      (node (ref "R22") (pin "2") (pinfunction "2_2") (pintype "passive"))
    )
    (net (code "77") (name "/SUM8") (class "Default")
      (node (ref "DA3") (pin "7") (pinfunction "IN2_7") (pintype "input"))
      (node (ref "R19") (pin "2") (pinfunction "2_2") (pintype "passive"))
    )
    (net (code "78") (name "/SUM_A") (class "Default")
      (node (ref "C24") (pin "2") (pinfunction "2_2") (pintype "passive"))
      (node (ref "IC4") (pin "1") (pinfunction "OUT_1") (pintype "output"))
      (node (ref "R37") (pin "1") (pinfunction "1_1") (pintype "passive"))
      (node (ref "R79") (pin "2") (pinfunction "2_2") (pintype "passive"))
      (node (ref "U$3") (pin "13") (pinfunction "13_13") (pintype "passive"))
    )
    (net (code "79") (name "/SUM_B") (class "Default")
      (node (ref "C25") (pin "2") (pinfunction "2_2") (pintype "passive"))
      (node (ref "IC4") (pin "14") (pinfunction "OUT_14") (pintype "output"))
      (node (ref "R28") (pin "1") (pinfunction "1_1") (pintype "passive"))
      (node (ref "R80") (pin "2") (pinfunction "2_2") (pintype "passive"))
      (node (ref "U$3") (pin "14") (pinfunction "14_14") (pintype "passive"))
    )
    (net (code "80") (name "/SUM_FX_A") (class "Default")
      (node (ref "C26") (pin "2") (pinfunction "2_2") (pintype "passive"))
      (node (ref "IC4") (pin "7") (pinfunction "OUT_7") (pintype "output"))
      (node (ref "R34") (pin "1") (pinfunction "1_1") (pintype "passive"))
      (node (ref "R81") (pin "2") (pinfunction "2_2") (pintype "passive"))
    )
    (net (code "81") (name "/SUM_FX_B") (class "Default")
      (node (ref "C27") (pin "2") (pinfunction "2_2") (pintype "passive"))
      (node (ref "IC4") (pin "8") (pinfunction "OUT_8") (pintype "output"))
      (node (ref "R31") (pin "1") (pinfunction "1_1") (pintype "passive"))
      (node (ref "R82") (pin "2") (pinfunction "2_2") (pintype "passive"))
    )
    (net (code "82") (name "/SVF_CHAIN") (class "Default")
      (node (ref "R69") (pin "2") (pinfunction "2_2") (pintype "passive"))
      (node (ref "U$3") (pin "16") (pinfunction "16_16") (pintype "passive"))
    )
    (net (code "83") (name "/SW1A") (class "Default")
      (node (ref "IC8") (pin "2") (pinfunction "D_2") (pintype "bidirectional"))
      (node (ref "R59") (pin "2") (pinfunction "2_2") (pintype "passive"))
    )
    (net (code "84") (name "/SW1B") (class "Default")
      (node (ref "IC8") (pin "15") (pinfunction "D_15") (pintype "bidirectional"))
      (node (ref "R60") (pin "2") (pinfunction "2_2") (pintype "passive"))
    )
    (net (code "85") (name "/SW2A") (class "Default")
      (node (ref "IC8") (pin "7") (pinfunction "D_7") (pintype "bidirectional"))
      (node (ref "R53") (pin "2") (pinfunction "2_2") (pintype "passive"))
    )
    (net (code "86") (name "/SW2B") (class "Default")
      (node (ref "IC8") (pin "10") (pinfunction "D_10") (pintype "bidirectional"))
      (node (ref "R54") (pin "2") (pinfunction "2_2") (pintype "passive"))
    )
    (net (code "87") (name "/SW3A") (class "Default")
      (node (ref "IC9") (pin "2") (pinfunction "D_2") (pintype "bidirectional"))
      (node (ref "R57") (pin "2") (pinfunction "2_2") (pintype "passive"))
    )
    (net (code "88") (name "/SW3B") (class "Default")
      (node (ref "IC9") (pin "15") (pinfunction "D_15") (pintype "bidirectional"))
      (node (ref "R58") (pin "2") (pinfunction "2_2") (pintype "passive"))
    )
    (net (code "89") (name "/SW4A") (class "Default")
      (node (ref "IC9") (pin "7") (pinfunction "D_7") (pintype "bidirectional"))
      (node (ref "R55") (pin "2") (pinfunction "2_2") (pintype "passive"))
    )
    (net (code "90") (name "/SW4B") (class "Default")
      (node (ref "IC9") (pin "10") (pinfunction "D_10") (pintype "bidirectional"))
      (node (ref "R56") (pin "2") (pinfunction "2_2") (pintype "passive"))
    )
    (net (code "91") (name "/SW5A") (class "Default")
      (node (ref "IC10") (pin "2") (pinfunction "D_2") (pintype "bidirectional"))
      (node (ref "R67") (pin "2") (pinfunction "2_2") (pintype "passive"))
    )
    (net (code "92") (name "/SW5B") (class "Default")
      (node (ref "IC10") (pin "15") (pinfunction "D_15") (pintype "bidirectional"))
      (node (ref "R68") (pin "2") (pinfunction "2_2") (pintype "passive"))
    )
    (net (code "93") (name "/SW6A") (class "Default")
      (node (ref "IC10") (pin "7") (pinfunction "D_7") (pintype "bidirectional"))
      (node (ref "R61") (pin "2") (pinfunction "2_2") (pintype "passive"))
    )
    (net (code "94") (name "/SW6B") (class "Default")
      (node (ref "IC10") (pin "10") (pinfunction "D_10") (pintype "bidirectional"))
      (node (ref "R62") (pin "2") (pinfunction "2_2") (pintype "passive"))
    )
    (net (code "95") (name "/SW7A") (class "Default")
      (node (ref "IC11") (pin "2") (pinfunction "D_2") (pintype "bidirectional"))
      (node (ref "R65") (pin "2") (pinfunction "2_2") (pintype "passive"))
    )
    (net (code "96") (name "/SW7B") (class "Default")
      (node (ref "IC11") (pin "15") (pinfunction "D_15") (pintype "bidirectional"))
      (node (ref "R66") (pin "2") (pinfunction "2_2") (pintype "passive"))
    )
    (net (code "97") (name "/SW8A") (class "Default")
      (node (ref "IC11") (pin "7") (pinfunction "D_7") (pintype "bidirectional"))
      (node (ref "R63") (pin "2") (pinfunction "2_2") (pintype "passive"))
    )
    (net (code "98") (name "/SW8B") (class "Default")
      (node (ref "IC11") (pin "10") (pinfunction "D_10") (pintype "bidirectional"))
      (node (ref "R64") (pin "2") (pinfunction "2_2") (pintype "passive"))
    )
    (net (code "99") (name "/VL") (class "Default")
      (node (ref "IC10") (pin "12") (pinfunction "VL_12") (pintype "bidirectional"))
      (node (ref "IC11") (pin "12") (pinfunction "VL_12") (pintype "bidirectional"))
      (node (ref "IC8") (pin "12") (pinfunction "VL_12") (pintype "bidirectional"))
      (node (ref "IC9") (pin "12") (pinfunction "VL_12") (pintype "bidirectional"))
      (node (ref "R77") (pin "2") (pinfunction "2_2") (pintype "passive"))
      (node (ref "R78") (pin "1") (pinfunction "1_1") (pintype "passive"))
    )
    (net (code "100") (name "/~{RST}") (class "Default")
      (node (ref "IC1") (pin "3") (pinfunction "~{RESET}_3") (pintype "bidirectional"))
      (node (ref "R1") (pin "2") (pinfunction "2_2") (pintype "passive"))
    )
    (net (code "101") (name "GND") (class "Default")
      (node (ref "C1") (pin "1") (pinfunction "1_1") (pintype "passive"))
      (node (ref "C10") (pin "2") (pinfunction "2_2") (pintype "passive"))
      (node (ref "C11") (pin "1") (pinfunction "1_1") (pintype "passive"))
      (node (ref "C12") (pin "2") (pinfunction "2_2") (pintype "passive"))
      (node (ref "C13") (pin "1") (pinfunction "1_1") (pintype "passive"))
      (node (ref "C14") (pin "1") (pinfunction "1_1") (pintype "passive"))
      (node (ref "C15") (pin "1") (pinfunction "1_1") (pintype "passive"))
      (node (ref "C16") (pin "1") (pinfunction "1_1") (pintype "passive"))
      (node (ref "C17") (pin "2") (pinfunction "2_2") (pintype "passive"))
      (node (ref "C18") (pin "2") (pinfunction "2_2") (pintype "passive"))
      (node (ref "C19") (pin "1") (pinfunction "1_1") (pintype "passive"))
      (node (ref "C2") (pin "2") (pinfunction "2_2") (pintype "passive"))
      (node (ref "C20") (pin "2") (pinfunction "2_2") (pintype "passive"))
      (node (ref "C21") (pin "1") (pinfunction "1_1") (pintype "passive"))
      (node (ref "C22") (pin "2") (pinfunction "2_2") (pintype "passive"))
      (node (ref "C23") (pin "1") (pinfunction "1_1") (pintype "passive"))
      (node (ref "C28") (pin "1") (pinfunction "1_1") (pintype "passive"))
      (node (ref "C29") (pin "2") (pinfunction "2_2") (pintype "passive"))
      (node (ref "C3") (pin "1") (pinfunction "1_1") (pintype "passive"))
      (node (ref "C30") (pin "1") (pinfunction "1_1") (pintype "passive"))
      (node (ref "C31") (pin "2") (pinfunction "2_2") (pintype "passive"))
      (node (ref "C32") (pin "1") (pinfunction "1_1") (pintype "passive"))
      (node (ref "C4") (pin "2") (pinfunction "2_2") (pintype "passive"))
      (node (ref "C5") (pin "1") (pinfunction "1_1") (pintype "passive"))
      (node (ref "C6") (pin "2") (pinfunction "2_2") (pintype "passive"))
      (node (ref "C7") (pin "1") (pinfunction "1_1") (pintype "passive"))
      (node (ref "C8") (pin "2") (pinfunction "2_2") (pintype "passive"))
      (node (ref "C9") (pin "1") (pinfunction "1_1") (pintype "passive"))
      (node (ref "DA1") (pin "8") (pinfunction "GND_8") (pintype "power_in"))
      (node (ref "DA2") (pin "8") (pinfunction "GND_8") (pintype "power_in"))
      (node (ref "DA3") (pin "8") (pinfunction "GND_8") (pintype "power_in"))
      (node (ref "IC1") (pin "12") (pinfunction "VSS_12") (pintype "power_in"))
      (node (ref "IC1") (pin "2") (pinfunction "A1_2") (pintype "bidirectional"))
      (node (ref "IC1") (pin "21") (pinfunction "A0_21") (pintype "bidirectional"))
      (node (ref "IC10") (pin "5") (pinfunction "AGND_5") (pintype "power_in"))
      (node (ref "IC11") (pin "5") (pinfunction "AGND_5") (pintype "power_in"))
      (node (ref "IC2") (pin "10") (pinfunction "+IN_10") (pintype "input"))
      (node (ref "IC2") (pin "12") (pinfunction "+IN_12") (pintype "input"))
      (node (ref "IC2") (pin "3") (pinfunction "+IN_3") (pintype "input"))
      (node (ref "IC3") (pin "3") (pinfunction "+IN_3") (pintype "input"))
      (node (ref "IC3") (pin "5") (pinfunction "+IN_5") (pintype "input"))
      (node (ref "IC4") (pin "10") (pinfunction "+IN_10") (pintype "input"))
      (node (ref "IC4") (pin "12") (pinfunction "+IN_12") (pintype "input"))
      (node (ref "IC4") (pin "3") (pinfunction "+IN_3") (pintype "input"))
      (node (ref "IC4") (pin "5") (pinfunction "+IN_5") (pintype "input"))
      (node (ref "IC7") (pin "10") (pinfunction "+IN_10") (pintype "input"))
      (node (ref "IC7") (pin "12") (pinfunction "+IN_12") (pintype "input"))
      (node (ref "IC7") (pin "3") (pinfunction "+IN_3") (pintype "input"))
      (node (ref "IC7") (pin "5") (pinfunction "+IN_5") (pintype "input"))
      (node (ref "IC8") (pin "5") (pinfunction "AGND_5") (pintype "power_in"))
      (node (ref "IC9") (pin "5") (pinfunction "AGND_5") (pintype "power_in"))
      (node (ref "R12") (pin "1") (pinfunction "1_1") (pintype "passive"))
      (node (ref "R15") (pin "1") (pinfunction "1_1") (pintype "passive"))
      (node (ref "R18") (pin "1") (pinfunction "1_1") (pintype "passive"))
      (node (ref "R21") (pin "1") (pinfunction "1_1") (pintype "passive"))
      (node (ref "R24") (pin "1") (pinfunction "1_1") (pintype "passive"))
      (node (ref "R27") (pin "1") (pinfunction "1_1") (pintype "passive"))
      (node (ref "R3") (pin "1") (pinfunction "1_1") (pintype "passive"))
      (node (ref "R30") (pin "1") (pinfunction "1_1") (pintype "passive"))
      (node (ref "R33") (pin "1") (pinfunction "1_1") (pintype "passive"))
      (node (ref "R36") (pin "1") (pinfunction "1_1") (pintype "passive"))
      (node (ref "R46") (pin "2") (pinfunction "2_2") (pintype "passive"))
      (node (ref "R47") (pin "2") (pinfunction "2_2") (pintype "passive"))
      (node (ref "R49") (pin "2") (pinfunction "2_2") (pintype "passive"))
      (node (ref "R6") (pin "1") (pinfunction "1_1") (pintype "passive"))
      (node (ref "R73") (pin "1") (pinfunction "1_1") (pintype "passive"))
      (node (ref "R74") (pin "1") (pinfunction "1_1") (pintype "passive"))
      (node (ref "R75") (pin "1") (pinfunction "1_1") (pintype "passive"))
      (node (ref "R76") (pin "1") (pinfunction "1_1") (pintype "passive"))
      (node (ref "R78") (pin "2") (pinfunction "2_2") (pintype "passive"))
      (node (ref "R9") (pin "1") (pinfunction "1_1") (pintype "passive"))
      (node (ref "U$2") (pin "7") (pinfunction "7_7") (pintype "passive"))
      (node (ref "U$3") (pin "4") (pinfunction "4_4") (pintype "passive"))
    )
    (net (code "102") (name "Net-(C13-Pad2)") (class "Default")
      (node (ref "C13") (pin "2") (pinfunction "2_2") (pintype "passive"))
      (node (ref "R38") (pin "1") (pinfunction "1_1") (pintype "passive"))
    )
    (net (code "103") (name "Net-(C14-Pad2)") (class "Default")
      (node (ref "C14") (pin "2") (pinfunction "2_2") (pintype "passive"))
      (node (ref "R39") (pin "1") (pinfunction "1_1") (pintype "passive"))
    )
    (net (code "104") (name "Net-(C15-Pad2)") (class "Default")
      (node (ref "C15") (pin "2") (pinfunction "2_2") (pintype "passive"))
      (node (ref "R40") (pin "1") (pinfunction "1_1") (pintype "passive"))
    )
    (net (code "105") (name "Net-(DA1B-CV2)") (class "Default")
      (node (ref "DA1") (pin "6") (pinfunction "CV2_6") (pintype "input"))
      (node (ref "R29") (pin "2") (pinfunction "2_2") (pintype "passive"))
      (node (ref "R30") (pin "2") (pinfunction "2_2") (pintype "passive"))
    )
    (net (code "106") (name "Net-(DA1B-CV3)") (class "Default")
      (node (ref "DA1") (pin "11") (pinfunction "CV3_11") (pintype "input"))
      (node (ref "R32") (pin "2") (pinfunction "2_2") (pintype "passive"))
      (node (ref "R33") (pin "2") (pinfunction "2_2") (pintype "passive"))
    )
    (net (code "107") (name "Net-(DA1B-CV4)") (class "Default")
      (node (ref "DA1") (pin "14") (pinfunction "CV4_14") (pintype "input"))
      (node (ref "R35") (pin "2") (pinfunction "2_2") (pintype "passive"))
      (node (ref "R36") (pin "2") (pinfunction "2_2") (pintype "passive"))
    )
    (net (code "108") (name "Net-(DA1B-OUT1)") (class "Default")
      (node (ref "DA1") (pin "4") (pinfunction "OUT1_4") (pintype "output"))
      (node (ref "IC7") (pin "13") (pinfunction "-IN_13") (pintype "input"))
      (node (ref "R51") (pin "2") (pinfunction "2_2") (pintype "passive"))
    )
    (net (code "109") (name "Net-(DA1B-OUT2)") (class "Default")
      (node (ref "DA1") (pin "5") (pinfunction "OUT2_5") (pintype "output"))
      (node (ref "IC2") (pin "9") (pinfunction "-IN_9") (pintype "input"))
      (node (ref "R50") (pin "2") (pinfunction "2_2") (pintype "passive"))
      (node (ref "R69") (pin "1") (pinfunction "1_1") (pintype "passive"))
      (node (ref "R71") (pin "1") (pinfunction "1_1") (pintype "passive"))
    )
    (net (code "110") (name "Net-(DA1B-OUT3)") (class "Default")
      (node (ref "DA1") (pin "12") (pinfunction "OUT3_12") (pintype "output"))
      (node (ref "IC2") (pin "6") (pinfunction "-IN_6") (pintype "input"))
      (node (ref "R52") (pin "2") (pinfunction "2_2") (pintype "passive"))
    )
    (net (code "111") (name "Net-(DA1B-OUT4)") (class "Default")
      (node (ref "DA1") (pin "13") (pinfunction "OUT4_13") (pintype "output"))
      (node (ref "IC2") (pin "5") (pinfunction "+IN_5") (pintype "input"))
      (node (ref "R49") (pin "1") (pinfunction "1_1") (pintype "passive"))
    )
    (net (code "112") (name "Net-(DA1B-VREF)") (class "Default")
      (node (ref "DA1") (pin "1") (pinfunction "VREF_1") (pintype "output"))
      (node (ref "R40") (pin "2") (pinfunction "2_2") (pintype "passive"))
    )
    (net (code "113") (name "Net-(DA2B-CV2)") (class "Default")
      (node (ref "DA2") (pin "6") (pinfunction "CV2_6") (pintype "input"))
      (node (ref "R5") (pin "2") (pinfunction "2_2") (pintype "passive"))
      (node (ref "R6") (pin "2") (pinfunction "2_2") (pintype "passive"))
    )
    (net (code "114") (name "Net-(DA2B-CV3)") (class "Default")
      (node (ref "DA2") (pin "11") (pinfunction "CV3_11") (pintype "input"))
      (node (ref "R8") (pin "2") (pinfunction "2_2") (pintype "passive"))
      (node (ref "R9") (pin "2") (pinfunction "2_2") (pintype "passive"))
    )
    (net (code "115") (name "Net-(DA2B-CV4)") (class "Default")
      (node (ref "DA2") (pin "14") (pinfunction "CV4_14") (pintype "input"))
      (node (ref "R11") (pin "2") (pinfunction "2_2") (pintype "passive"))
      (node (ref "R12") (pin "2") (pinfunction "2_2") (pintype "passive"))
    )
    (net (code "116") (name "Net-(DA2B-VREF)") (class "Default")
      (node (ref "DA2") (pin "1") (pinfunction "VREF_1") (pintype "output"))
      (node (ref "R38") (pin "2") (pinfunction "2_2") (pintype "passive"))
    )
    (net (code "117") (name "Net-(DA3B-CV2)") (class "Default")
      (node (ref "DA3") (pin "6") (pinfunction "CV2_6") (pintype "input"))
      (node (ref "R17") (pin "2") (pinfunction "2_2") (pintype "passive"))
      (node (ref "R18") (pin "2") (pinfunction "2_2") (pintype "passive"))
    )
    (net (code "118") (name "Net-(DA3B-CV3)") (class "Default")
      (node (ref "DA3") (pin "11") (pinfunction "CV3_11") (pintype "input"))
      (node (ref "R20") (pin "2") (pinfunction "2_2") (pintype "passive"))
      (node (ref "R21") (pin "2") (pinfunction "2_2") (pintype "passive"))
    )
    (net (code "119") (name "Net-(DA3B-CV4)") (class "Default")
      (node (ref "DA3") (pin "14") (pinfunction "CV4_14") (pintype "input"))
      (node (ref "R23") (pin "2") (pinfunction "2_2") (pintype "passive"))
      (node (ref "R24") (pin "2") (pinfunction "2_2") (pintype "passive"))
    )
    (net (code "120") (name "Net-(DA3B-OUT2)") (class "Default")
      (node (ref "DA3") (pin "5") (pinfunction "OUT2_5") (pintype "output"))
      (node (ref "IC6") (pin "3") (pinfunction "+IN_3") (pintype "input"))
      (node (ref "R46") (pin "1") (pinfunction "1_1") (pintype "passive"))
    )
    (net (code "121") (name "Net-(DA3B-VREF)") (class "Default")
      (node (ref "DA3") (pin "1") (pinfunction "VREF_1") (pintype "output"))
      (node (ref "R39") (pin "2") (pinfunction "2_2") (pintype "passive"))
    )
    (net (code "122") (name "Net-(IC1-IO0_0)") (class "Default")
      (node (ref "IC1") (pin "4") (pinfunction "IO0_0_4") (pintype "bidirectional"))
      (node (ref "R72") (pin "1") (pinfunction "1_1") (pintype "passive"))
    )
    (net (code "123") (name "Net-(IC1-IO0_1)") (class "Default")
      (node (ref "IC1") (pin "5") (pinfunction "IO0_1_5") (pintype "bidirectional"))
      (node (ref "R83") (pin "1") (pinfunction "1_1") (pintype "passive"))
    )
    (net (code "124") (name "Net-(IC1-IO0_2)") (class "Default")
      (node (ref "IC1") (pin "6") (pinfunction "IO0_2_6") (pintype "bidirectional"))
      (node (ref "R84") (pin "1") (pinfunction "1_1") (pintype "passive"))
    )
    (net (code "125") (name "Net-(IC1-IO0_3)") (class "Default")
      (node (ref "IC1") (pin "7") (pinfunction "IO0_3_7") (pintype "bidirectional"))
      (node (ref "R85") (pin "1") (pinfunction "1_1") (pintype "passive"))
    )
    (net (code "126") (name "Net-(IC1-IO0_4)") (class "Default")
      (node (ref "IC1") (pin "8") (pinfunction "IO0_4_8") (pintype "bidirectional"))
      (node (ref "R86") (pin "1") (pinfunction "1_1") (pintype "passive"))
    )
    (net (code "127") (name "Net-(IC1-IO0_5)") (class "Default")
      (node (ref "IC1") (pin "9") (pinfunction "IO0_5_9") (pintype "bidirectional"))
      (node (ref "R87") (pin "1") (pinfunction "1_1") (pintype "passive"))
    )
    (net (code "128") (name "Net-(IC1-IO0_6)") (class "Default")
      (node (ref "IC1") (pin "10") (pinfunction "IO0_6_10") (pintype "bidirectional"))
      (node (ref "R88") (pin "1") (pinfunction "1_1") (pintype "passive"))
    )
    (net (code "129") (name "Net-(IC1-IO0_7)") (class "Default")
      (node (ref "IC1") (pin "11") (pinfunction "IO0_7_11") (pintype "bidirectional"))
      (node (ref "R89") (pin "1") (pinfunction "1_1") (pintype "passive"))
    )
    (net (code "130") (name "Net-(IC1-IO1_0)") (class "Default")
      (node (ref "IC1") (pin "13") (pinfunction "IO1_0_13") (pintype "bidirectional"))
      (node (ref "R90") (pin "1") (pinfunction "1_1") (pintype "passive"))
    )
    (net (code "131") (name "Net-(IC1-IO1_1)") (class "Default")
      (node (ref "IC1") (pin "14") (pinfunction "IO1_1_14") (pintype "bidirectional"))
      (node (ref "R91") (pin "1") (pinfunction "1_1") (pintype "passive"))
    )
    (net (code "132") (name "Net-(IC1-IO1_2)") (class "Default")
      (node (ref "IC1") (pin "15") (pinfunction "IO1_2_15") (pintype "bidirectional"))
      (node (ref "R92") (pin "1") (pinfunction "1_1") (pintype "passive"))
    )
    (net (code "133") (name "Net-(IC1-IO1_3)") (class "Default")
      (node (ref "IC1") (pin "16") (pinfunction "IO1_3_16") (pintype "bidirectional"))
      (node (ref "R93") (pin "1") (pinfunction "1_1") (pintype "passive"))
    )
    (net (code "134") (name "Net-(IC1-IO1_4)") (class "Default")
      (node (ref "IC1") (pin "17") (pinfunction "IO1_4_17") (pintype "bidirectional"))
      (node (ref "R94") (pin "1") (pinfunction "1_1") (pintype "passive"))
    )
    (net (code "135") (name "Net-(IC1-IO1_5)") (class "Default")
      (node (ref "IC1") (pin "18") (pinfunction "IO1_5_18") (pintype "bidirectional"))
      (node (ref "R95") (pin "1") (pinfunction "1_1") (pintype "passive"))
    )
    (net (code "136") (name "Net-(IC1-IO1_6)") (class "Default")
      (node (ref "IC1") (pin "19") (pinfunction "IO1_6_19") (pintype "bidirectional"))
      (node (ref "R96") (pin "1") (pinfunction "1_1") (pintype "passive"))
    )
    (net (code "137") (name "Net-(IC1-IO1_7)") (class "Default")
      (node (ref "IC1") (pin "20") (pinfunction "IO1_7_20") (pintype "bidirectional"))
      (node (ref "R97") (pin "1") (pinfunction "1_1") (pintype "passive"))
    )
    (net (code "138") (name "Net-(IC7A--IN)") (class "Default")
      (node (ref "IC7") (pin "1") (pinfunction "OUT_1") (pintype "output"))
      (node (ref "IC7") (pin "2") (pinfunction "-IN_2") (pintype "input"))
    )
    (net (code "139") (name "Net-(IC7D-OUT)") (class "Default")
      (node (ref "IC7") (pin "14") (pinfunction "OUT_14") (pintype "output"))
      (node (ref "R51") (pin "1") (pinfunction "1_1") (pintype "passive"))
      (node (ref "R71") (pin "2") (pinfunction "2_2") (pintype "passive"))
    )
    (net (code "140") (name "unconnected-(IC1-~{INT}-Pad1)") (class "Default")
      (node (ref "IC1") (pin "1") (pinfunction "~{INT}_1") (pintype "bidirectional"))
    )
  )
)
